# ModuloMQTT.net
KiCad netlist of a schematic drawn in Altium Designer
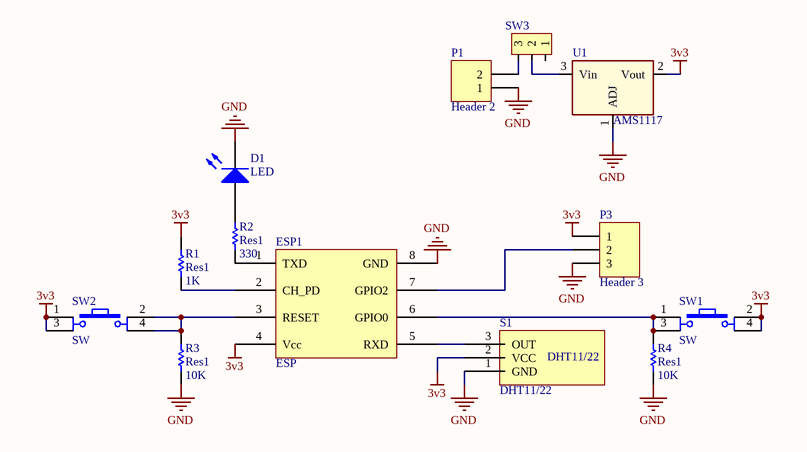
[diagram p0: ModuloMQTT.SchDoc]

(export (version "E")
  (design (tool "Eeschema 10.0.6"))
  (components
    (comp (ref "D1")
      (value "LED")
      (footprint "LED-0 5mm BLUE")
      (description "Typical LED")
      (fields (field (name "PUBLISHER") "Altium Limited"))
      (libsource (lib "hphonglib") (part "LED"))
    )
    (comp (ref "ESP1") (value "ESP") (footprint "ESP") (libsource (lib "Erick") (part "ESP")))
    (comp (ref "P1")
      (value "Header 2")
      (footprint "Header 2")
      (description "Header, 2-Pin")
      (fields (field (name "PUBLISHER") "Altium Limited"))
      (libsource (lib "hphonglib") (part "Header 2"))
    )
    (comp (ref "P3")
      (value "Header 3")
      (footprint "Header 3")
      (description "Header, 3-Pin")
      (fields (field (name "PUBLISHER") "Altium Limited"))
      (libsource (lib "hphonglib") (part "Header 3"))
    )
    (comp (ref "R1")
      (value "Res1")
      (footprint "AXIAL-0.3")
      (description "Resistor")
      (fields (field (name "ALTIUM_VALUE") "1K") (field (name "PUBLISHER") "Altium Limited"))
      (libsource (lib "Miscellaneous Devices") (part "Res1"))
    )
    (comp (ref "R2")
      (value "Res1")
      (footprint "AXIAL-0.3")
      (description "Resistor")
      (fields (field (name "ALTIUM_VALUE") "330") (field (name "PUBLISHER") "Altium Limited"))
      (libsource (lib "Miscellaneous Devices") (part "Res1"))
    )
    (comp (ref "R3")
      (value "Res1")
      (footprint "AXIAL-0.3")
      (description "Resistor")
      (fields (field (name "ALTIUM_VALUE") "10K") (field (name "PUBLISHER") "Altium Limited"))
      (libsource (lib "Miscellaneous Devices") (part "Res1"))
    )
    (comp (ref "R4")
      (value "Res1")
      (footprint "AXIAL-0.3")
      (description "Resistor")
      (fields (field (name "ALTIUM_VALUE") "10K") (field (name "PUBLISHER") "Altium Limited"))
      (libsource (lib "Miscellaneous Devices") (part "Res1"))
    )
    (comp (ref "S1") (value "DHT11/22") (footprint "Header 3") (libsource (lib "Erick") (part "DHT11/22")))
    (comp (ref "SW1")
      (value "SW")
      (footprint "SW4")
      (description "Switch button 4 pin")
      (libsource (lib "hanguyen") (part "SW4"))
    )
    (comp (ref "SW2")
      (value "SW")
      (footprint "SW4")
      (description "Switch button 4 pin")
      (libsource (lib "hanguyen") (part "SW4"))
    )
    (comp (ref "SW3") (value "SW3") (footprint "Header 3") (libsource (lib "hphonglib") (part "SW3")))
    (comp (ref "U1")
      (value "AMS1117")
      (footprint "AMS1117_No_SMD")
      (description "Regulator SMD Chip")
      (fields (field (name "PUBLISHER") "Hoang Nguyen"))
      (libsource (lib "hphonglib") (part "AMS1117"))
    )
  )
  (nets
    (net (code "1") (name "3v3") (class "Default")
      (node (ref "ESP1") (pin "4") (pinfunction "Vcc_4") (pintype "passive"))
      (node (ref "P3") (pin "1") (pinfunction "1_1") (pintype "passive"))
      (node (ref "R1") (pin "1") (pinfunction "1_1") (pintype "passive"))
      (node (ref "S1") (pin "2") (pinfunction "VCC_2") (pintype "passive"))
      (node (ref "SW1") (pin "2") (pintype "passive"))
      (node (ref "SW1") (pin "4") (pintype "passive"))
      (node (ref "SW2") (pin "1") (pintype "passive"))
      (node (ref "SW2") (pin "3") (pintype "passive"))
      (node (ref "U1") (pin "2") (pinfunction "Vout_2") (pintype "passive"))
    )
    (net (code "2") (name "GND") (class "Default")
      (node (ref "D1") (pin "2") (pinfunction "K_2") (pintype "passive"))
      (node (ref "ESP1") (pin "8") (pinfunction "GND_8") (pintype "passive"))
      (node (ref "P1") (pin "1") (pinfunction "1_1") (pintype "passive"))
      (node (ref "P3") (pin "3") (pinfunction "3_3") (pintype "passive"))
      (node (ref "R3") (pin "1") (pinfunction "1_1") (pintype "passive"))
      (node (ref "R4") (pin "1") (pinfunction "1_1") (pintype "passive"))
      (node (ref "S1") (pin "1") (pinfunction "GND_1") (pintype "passive"))
      (node (ref "U1") (pin "1") (pinfunction "ADJ_1") (pintype "passive"))
    )
    (net (code "3") (name "Net-(D1-A)") (class "Default")
      (node (ref "D1") (pin "1") (pinfunction "A_1") (pintype "passive"))
      (node (ref "R2") (pin "2") (pinfunction "2_2") (pintype "passive"))
    )
    (net (code "4") (name "Net-(ESP1-CH_PD)") (class "Default")
      (node (ref "ESP1") (pin "2") (pinfunction "CH_PD_2") (pintype "passive"))
      (node (ref "R1") (pin "2") (pinfunction "2_2") (pintype "passive"))
    )
    (net (code "5") (name "Net-(ESP1-GPIO0)") (class "Default")
      (node (ref "ESP1") (pin "6") (pinfunction "GPIO0_6") (pintype "passive"))
      (node (ref "R4") (pin "2") (pinfunction "2_2") (pintype "passive"))
      (node (ref "SW1") (pin "1") (pintype "passive"))
      (node (ref "SW1") (pin "3") (pintype "passive"))
    )
    (net (code "6") (name "Net-(ESP1-GPIO2)") (class "Default")
      (node (ref "ESP1") (pin "7") (pinfunction "GPIO2_7") (pintype "passive"))
      (node (ref "P3") (pin "2") (pinfunction "2_2") (pintype "passive"))
    )
    (net (code "7") (name "Net-(ESP1-RESET)") (class "Default")
      (node (ref "ESP1") (pin "3") (pinfunction "RESET_3") (pintype "passive"))
      (node (ref "R3") (pin "2") (pinfunction "2_2") (pintype "passive"))
      (node (ref "SW2") (pin "2") (pintype "passive"))
      (node (ref "SW2") (pin "4") (pintype "passive"))
    )
    (net (code "8") (name "Net-(ESP1-RXD)") (class "Default")
      (node (ref "ESP1") (pin "5") (pinfunction "RXD_5") (pintype "passive"))
      (node (ref "S1") (pin "3") (pinfunction "OUT_3") (pintype "passive"))
    )
    (net (code "9") (name "Net-(ESP1-TXD)") (class "Default")
      (node (ref "ESP1") (pin "1") (pinfunction "TXD_1") (pintype "passive"))
      (node (ref "R2") (pin "1") (pinfunction "1_1") (pintype "passive"))
    )
    (net (code "10") (name "Net-(P1-Pad2)") (class "Default")
      (node (ref "P1") (pin "2") (pinfunction "2_2") (pintype "passive"))
      (node (ref "SW3") (pin "3") (pinfunction "3_3") (pintype "passive"))
    )
    (net (code "11") (name "Net-(U1-Vin)") (class "Default")
      (node (ref "SW3") (pin "2") (pinfunction "2_2") (pintype "passive"))
      (node (ref "U1") (pin "3") (pinfunction "Vin_3") (pintype "passive"))
    )
    (net (code "12") (name "unconnected-(SW3-Pad1)") (class "Default")
      (node (ref "SW3") (pin "1") (pinfunction "1_1") (pintype "passive"))
    )
  )
)
